# CLASS1.net
KiCad netlist of a schematic drawn in Altium Designer
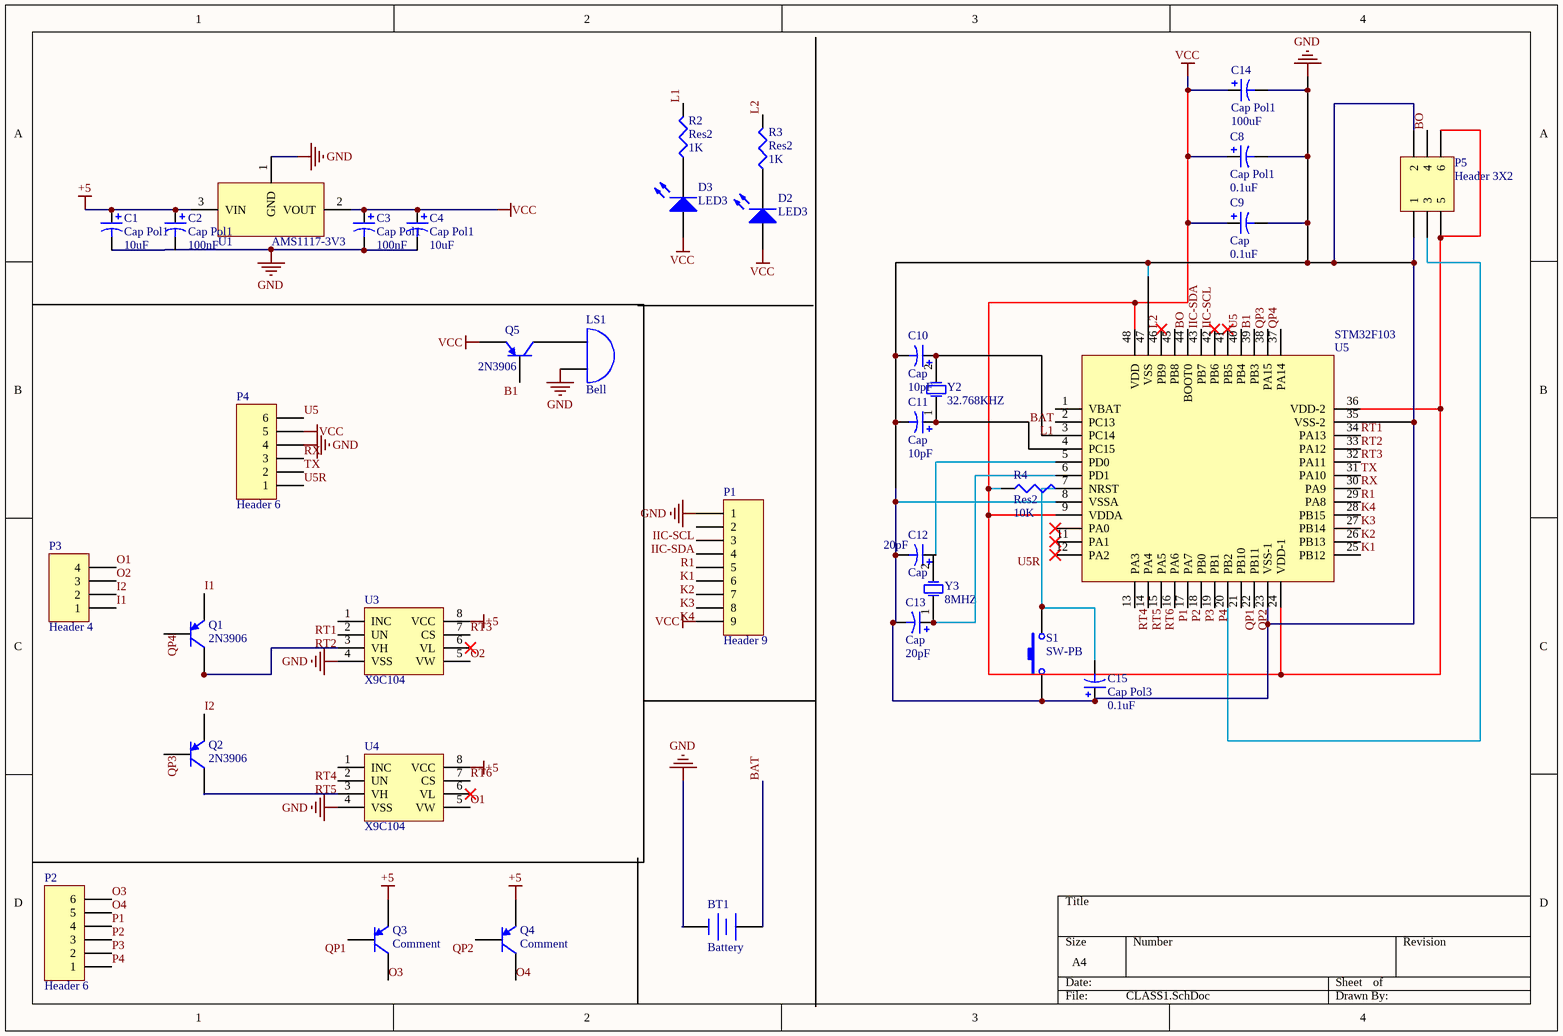
[diagram p0: CLASS1.SchDoc]

(export (version "E")
  (design (tool "Eeschema 10.0.6"))
  (components
    (comp (ref "BT1")
      (value "Battery")
      (footprint "BAT-2")
      (description "Multicell Battery")
      (fields (field (name "PUBLISHER") "Altium Limited"))
      (libsource (lib "Miscellaneous Devices") (part "Battery"))
    )
    (comp (ref "C1")
      (value "Cap Pol1")
      (footprint "C0805")
      (description "Polarized Capacitor (Surface Mount)")
      (fields (field (name "ALTIUM_VALUE") "10uF") (field (name "PUBLISHER") "Altium Limited"))
      (libsource (lib "Miscellaneous Devices") (part "Cap Pol3"))
    )
    (comp (ref "C2")
      (value "Cap Pol1")
      (footprint "C0805")
      (description "Polarized Capacitor (Surface Mount)")
      (fields (field (name "ALTIUM_VALUE") "100nF") (field (name "PUBLISHER") "Altium Limited"))
      (libsource (lib "Miscellaneous Devices") (part "Cap Pol3"))
    )
    (comp (ref "C3")
      (value "Cap Pol1")
      (footprint "C0805")
      (description "Polarized Capacitor (Surface Mount)")
      (fields (field (name "ALTIUM_VALUE") "100nF") (field (name "PUBLISHER") "Altium Limited"))
      (libsource (lib "Miscellaneous Devices") (part "Cap Pol3"))
    )
    (comp (ref "C4")
      (value "Cap Pol1")
      (footprint "C0805")
      (description "Polarized Capacitor (Surface Mount)")
      (fields (field (name "ALTIUM_VALUE") "10uF") (field (name "PUBLISHER") "Altium Limited"))
      (libsource (lib "Miscellaneous Devices") (part "Cap Pol3"))
    )
    (comp (ref "C8")
      (value "Cap Pol1")
      (footprint "C0805")
      (description "Polarized Capacitor (Surface Mount)")
      (fields (field (name "ALTIUM_VALUE") "0.1uF") (field (name "PUBLISHER") "Altium Limited"))
      (libsource (lib "Miscellaneous Devices") (part "Cap Pol3"))
    )
    (comp (ref "C9")
      (value "Cap")
      (footprint "C0805")
      (description "Polarized Capacitor (Surface Mount)")
      (fields (field (name "ALTIUM_VALUE") "0.1uF") (field (name "PUBLISHER") "Altium Limited"))
      (libsource (lib "Miscellaneous Devices") (part "Cap Pol3"))
    )
    (comp (ref "C10")
      (value "Cap")
      (footprint "C0805")
      (description "Polarized Capacitor (Surface Mount)")
      (fields (field (name "ALTIUM_VALUE") "10pF") (field (name "PUBLISHER") "Altium Limited"))
      (libsource (lib "Miscellaneous Devices") (part "Cap Pol3"))
    )
    (comp (ref "C11")
      (value "Cap")
      (footprint "C0805")
      (description "Polarized Capacitor (Surface Mount)")
      (fields (field (name "ALTIUM_VALUE") "10pF") (field (name "PUBLISHER") "Altium Limited"))
      (libsource (lib "Miscellaneous Devices") (part "Cap Pol3"))
    )
    (comp (ref "C12")
      (value "Cap")
      (footprint "C0805")
      (description "Polarized Capacitor (Surface Mount)")
      (fields (field (name "ALTIUM_VALUE") "20pF") (field (name "PUBLISHER") "Altium Limited"))
      (libsource (lib "Miscellaneous Devices") (part "Cap Pol3"))
    )
    (comp (ref "C13")
      (value "Cap")
      (footprint "C0805")
      (description "Polarized Capacitor (Surface Mount)")
      (fields (field (name "ALTIUM_VALUE") "20pF") (field (name "PUBLISHER") "Altium Limited"))
      (libsource (lib "Miscellaneous Devices") (part "Cap Pol3"))
    )
    (comp (ref "C14")
      (value "Cap Pol1")
      (footprint "A")
      (description "Polarized Capacitor (Radial)")
      (fields (field (name "ALTIUM_VALUE") "100uF") (field (name "PUBLISHER") "Altium Limited"))
      (libsource (lib "Miscellaneous Devices") (part "Cap Pol1"))
    )
    (comp (ref "C15")
      (value "Cap Pol3")
      (footprint "C0805")
      (description "Polarized Capacitor (Surface Mount)")
      (fields (field (name "ALTIUM_VALUE") "0.1uF") (field (name "PUBLISHER") "Altium Limited"))
      (libsource (lib "Miscellaneous Devices") (part "Cap Pol3"))
    )
    (comp (ref "D2")
      (value "LED3")
      (footprint "6-0805")
      (description "Typical BLUE SiC LED")
      (fields (field (name "PUBLISHER") "Altium Limited"))
      (libsource (lib "Miscellaneous Devices") (part "LED3"))
    )
    (comp (ref "D3")
      (value "LED3")
      (footprint "C0805")
      (description "Typical BLUE SiC LED")
      (fields (field (name "PUBLISHER") "Altium Limited"))
      (libsource (lib "Miscellaneous Devices") (part "LED3"))
    )
    (comp (ref "LS1")
      (value "Bell")
      (footprint "PIN2")
      (description "Electrical Bell")
      (fields (field (name "PUBLISHER") "Altium Limited"))
      (libsource (lib "Miscellaneous Devices") (part "Bell"))
    )
    (comp (ref "P1")
      (value "Header 9")
      (footprint "HDR1X9")
      (description "Header, 9-Pin")
      (fields (field (name "PUBLISHER") "Altium Limited"))
      (libsource (lib "Miscellaneous Connectors") (part "Header 9"))
    )
    (comp (ref "P2")
      (value "Header 6")
      (footprint "HDR1X6")
      (description "Header, 6-Pin")
      (fields (field (name "PUBLISHER") "Altium Limited"))
      (libsource (lib "Miscellaneous Connectors") (part "Header 6"))
    )
    (comp (ref "P3")
      (value "Header 4")
      (footprint "HDR1X4")
      (description "Header, 4-Pin")
      (fields (field (name "PUBLISHER") "Altium Limited"))
      (libsource (lib "Miscellaneous Connectors") (part "Header 4"))
    )
    (comp (ref "P4")
      (value "Header 6")
      (footprint "HDR1X6")
      (description "Header, 6-Pin")
      (fields (field (name "PUBLISHER") "Altium Limited"))
      (libsource (lib "Miscellaneous Connectors") (part "Header 6"))
    )
    (comp (ref "P5")
      (value "Header 3X2")
      (footprint "HDR2X3")
      (description "Header, 3-Pin, Dual row")
      (fields (field (name "PUBLISHER") "Altium Limited"))
      (libsource (lib "Miscellaneous Connectors") (part "Header 3X2"))
    )
    (comp (ref "Q1")
      (value "2N3906")
      (footprint "TO-92A")
      (description "PNP General Purpose Amplifier")
      (fields (field (name "PUBLISHER") "Altium Limited"))
      (libsource (lib "Miscellaneous Devices") (part "2N3906"))
    )
    (comp (ref "Q2")
      (value "2N3906")
      (footprint "TO-92A")
      (description "PNP General Purpose Amplifier")
      (fields (field (name "PUBLISHER") "Altium Limited"))
      (libsource (lib "Miscellaneous Devices") (part "2N3906"))
    )
    (comp (ref "Q3")
      (value "Comment")
      (footprint "TO-92A")
      (description "PNP General Purpose Amplifier")
      (fields (field (name "PUBLISHER") "Altium Limited"))
      (libsource (lib "Miscellaneous Devices") (part "2N3906"))
    )
    (comp (ref "Q4")
      (value "Comment")
      (footprint "TO-92A")
      (description "PNP General Purpose Amplifier")
      (fields (field (name "PUBLISHER") "Altium Limited"))
      (libsource (lib "Miscellaneous Devices") (part "2N3906"))
    )
    (comp (ref "Q5")
      (value "2N3906")
      (footprint "TO-92A")
      (description "PNP General Purpose Amplifier")
      (fields (field (name "PUBLISHER") "Altium Limited"))
      (libsource (lib "Miscellaneous Devices") (part "2N3906"))
    )
    (comp (ref "R2")
      (value "Res2")
      (footprint "J1-0603")
      (description "Resistor")
      (fields (field (name "ALTIUM_VALUE") "1K") (field (name "PUBLISHER") "Altium Limited"))
      (libsource (lib "Miscellaneous Devices") (part "Res3"))
    )
    (comp (ref "R3")
      (value "Res2")
      (footprint "J1-0603")
      (description "Resistor")
      (fields (field (name "ALTIUM_VALUE") "1K") (field (name "PUBLISHER") "Altium Limited"))
      (libsource (lib "Miscellaneous Devices") (part "Res3"))
    )
    (comp (ref "R4")
      (value "Res2")
      (footprint "J1-0603")
      (description "Resistor")
      (fields (field (name "ALTIUM_VALUE") "10K") (field (name "PUBLISHER") "Altium Limited"))
      (libsource (lib "Miscellaneous Devices") (part "Res3"))
    )
    (comp (ref "S1")
      (value "SW-PB")
      (footprint "SPST-2")
      (description "Switch")
      (fields (field (name "PUBLISHER") "Altium Limited"))
      (libsource (lib "Miscellaneous Devices") (part "SW-PB"))
    )
    (comp (ref "U1")
      (value "AMS1117-3V3")
      (footprint "AMS1117-3V3")
      (libsource (lib "Schlib STM") (part "AMS1117-3V3"))
    )
    (comp (ref "U3") (value "X9C104") (footprint "X9C104") (libsource (lib "Schlib STM") (part "xX9C104")))
    (comp (ref "U4") (value "X9C104") (footprint "X9C104") (libsource (lib "Schlib STM") (part "xX9C104")))
    (comp (ref "U5")
      (value "STM32F103")
      (footprint "STM32F103")
      (libsource (lib "Schlib STM") (part "STM32F103"))
    )
    (comp (ref "Y2")
      (value "32.768KHZ")
      (footprint "R38")
      (description "Crystal Oscillator")
      (fields (field (name "PUBLISHER") "Altium Limited"))
      (libsource (lib "Miscellaneous Devices") (part "XTAL"))
    )
    (comp (ref "Y3")
      (value "8MHZ")
      (footprint "R38")
      (description "Crystal Oscillator")
      (fields (field (name "PUBLISHER") "Altium Limited"))
      (libsource (lib "Miscellaneous Devices") (part "XTAL"))
    )
  )
  (nets
    (net (code "1") (name "+5") (class "Default")
      (node (ref "C1") (pin "1") (pinfunction "1_1") (pintype "passive"))
      (node (ref "C2") (pin "1") (pinfunction "1_1") (pintype "passive"))
      (node (ref "Q3") (pin "1") (pinfunction "E_1") (pintype "passive"))
      (node (ref "Q4") (pin "1") (pinfunction "E_1") (pintype "passive"))
      (node (ref "U1") (pin "3") (pinfunction "VIN_3") (pintype "power_in"))
      (node (ref "U3") (pin "8") (pinfunction "VCC_8") (pintype "power_in"))
      (node (ref "U4") (pin "8") (pinfunction "VCC_8") (pintype "power_in"))
    )
    (net (code "2") (name "/B1") (class "Default")
      (node (ref "Q5") (pin "2") (pinfunction "B_2") (pintype "passive"))
      (node (ref "U5") (pin "39") (pinfunction "PB3_39") (pintype "power_in"))
    )
    (net (code "3") (name "/BAT") (class "Default")
      (node (ref "BT1") (pin "1") (pinfunction "+_1") (pintype "passive"))
      (node (ref "U5") (pin "1") (pinfunction "VBAT_1") (pintype "power_in"))
    )
    (net (code "4") (name "/BO") (class "Default")
      (node (ref "P5") (pin "4") (pinfunction "4_4") (pintype "passive"))
      (node (ref "U5") (pin "44") (pinfunction "BOOT0_44") (pintype "power_in"))
    )
    (net (code "5") (name "/I1") (class "Default")
      (node (ref "P3") (pin "1") (pinfunction "1_1") (pintype "passive"))
      (node (ref "Q1") (pin "1") (pinfunction "E_1") (pintype "passive"))
    )
    (net (code "6") (name "/I2") (class "Default")
      (node (ref "P3") (pin "2") (pinfunction "2_2") (pintype "passive"))
      (node (ref "Q2") (pin "1") (pinfunction "E_1") (pintype "passive"))
    )
    (net (code "7") (name "/IIC-SCL") (class "Default")
      (node (ref "P1") (pin "2") (pinfunction "2_2") (pintype "passive"))
      (node (ref "U5") (pin "42") (pinfunction "PB6_42") (pintype "power_in"))
    )
    (net (code "8") (name "/IIC-SDA") (class "Default")
      (node (ref "P1") (pin "3") (pinfunction "3_3") (pintype "passive"))
      (node (ref "U5") (pin "43") (pinfunction "PB7_43") (pintype "power_in"))
    )
    (net (code "9") (name "/K1") (class "Default")
      (node (ref "P1") (pin "5") (pinfunction "5_5") (pintype "passive"))
      (node (ref "U5") (pin "25") (pinfunction "PB12_25") (pintype "power_in"))
    )
    (net (code "10") (name "/K2") (class "Default")
      (node (ref "P1") (pin "6") (pinfunction "6_6") (pintype "passive"))
      (node (ref "U5") (pin "26") (pinfunction "PB13_26") (pintype "power_in"))
    )
    (net (code "11") (name "/K3") (class "Default")
      (node (ref "P1") (pin "7") (pinfunction "7_7") (pintype "passive"))
      (node (ref "U5") (pin "27") (pinfunction "PB14_27") (pintype "power_in"))
    )
    (net (code "12") (name "/K4") (class "Default")
      (node (ref "P1") (pin "8") (pinfunction "8_8") (pintype "passive"))
      (node (ref "U5") (pin "28") (pinfunction "PB15_28") (pintype "power_in"))
    )
    (net (code "13") (name "/L1") (class "Default")
      (node (ref "R2") (pin "2") (pinfunction "2_2") (pintype "passive"))
      (node (ref "U5") (pin "2") (pinfunction "PC13_2") (pintype "power_in"))
    )
    (net (code "14") (name "/L2") (class "Default")
      (node (ref "R3") (pin "2") (pinfunction "2_2") (pintype "passive"))
      (node (ref "U5") (pin "46") (pinfunction "PB9_46") (pintype "power_in"))
    )
    (net (code "15") (name "/O1") (class "Default")
      (node (ref "P3") (pin "4") (pinfunction "4_4") (pintype "passive"))
      (node (ref "U4") (pin "5") (pinfunction "VW_5") (pintype "power_in"))
    )
    (net (code "16") (name "/O2") (class "Default")
      (node (ref "P3") (pin "3") (pinfunction "3_3") (pintype "passive"))
      (node (ref "U3") (pin "5") (pinfunction "VW_5") (pintype "power_in"))
    )
    (net (code "17") (name "/O3") (class "Default")
      (node (ref "P2") (pin "6") (pinfunction "6_6") (pintype "passive"))
      (node (ref "Q3") (pin "3") (pinfunction "C_3") (pintype "passive"))
    )
    (net (code "18") (name "/O4") (class "Default")
      (node (ref "P2") (pin "5") (pinfunction "5_5") (pintype "passive"))
      (node (ref "Q4") (pin "3") (pinfunction "C_3") (pintype "passive"))
    )
    (net (code "19") (name "/P1") (class "Default")
      (node (ref "P2") (pin "4") (pinfunction "4_4") (pintype "passive"))
      (node (ref "U5") (pin "16") (pinfunction "PA6_16") (pintype "power_in"))
    )
    (net (code "20") (name "/P2") (class "Default")
      (node (ref "P2") (pin "3") (pinfunction "3_3") (pintype "passive"))
      (node (ref "U5") (pin "17") (pinfunction "PA7_17") (pintype "power_in"))
    )
    (net (code "21") (name "/P3") (class "Default")
      (node (ref "P2") (pin "2") (pinfunction "2_2") (pintype "passive"))
      (node (ref "U5") (pin "18") (pinfunction "PB0_18") (pintype "power_in"))
    )
    (net (code "22") (name "/P4") (class "Default")
      (node (ref "P2") (pin "1") (pinfunction "1_1") (pintype "passive"))
      (node (ref "U5") (pin "19") (pinfunction "PB1_19") (pintype "power_in"))
    )
    (net (code "23") (name "/QP1") (class "Default")
      (node (ref "Q3") (pin "2") (pinfunction "B_2") (pintype "passive"))
      (node (ref "U5") (pin "21") (pinfunction "PB10_21") (pintype "power_in"))
    )
    (net (code "24") (name "/QP2") (class "Default")
      (node (ref "Q4") (pin "2") (pinfunction "B_2") (pintype "passive"))
      (node (ref "U5") (pin "22") (pinfunction "PB11_22") (pintype "power_in"))
    )
    (net (code "25") (name "/QP3") (class "Default")
      (node (ref "Q2") (pin "2") (pinfunction "B_2") (pintype "passive"))
      (node (ref "U5") (pin "38") (pinfunction "PA15_38") (pintype "power_in"))
    )
    (net (code "26") (name "/QP4") (class "Default")
      (node (ref "Q1") (pin "2") (pinfunction "B_2") (pintype "passive"))
      (node (ref "U5") (pin "37") (pinfunction "PA14_37") (pintype "power_in"))
    )
    (net (code "27") (name "/R1") (class "Default")
      (node (ref "P1") (pin "4") (pinfunction "4_4") (pintype "passive"))
      (node (ref "U5") (pin "29") (pinfunction "PA8_29") (pintype "power_in"))
    )
    (net (code "28") (name "/RT1") (class "Default")
      (node (ref "U3") (pin "1") (pinfunction "INC_1") (pintype "power_in"))
      (node (ref "U5") (pin "34") (pinfunction "PA13_34") (pintype "power_in"))
    )
    (net (code "29") (name "/RT2") (class "Default")
      (node (ref "U3") (pin "2") (pinfunction "UN_2") (pintype "power_in"))
      (node (ref "U5") (pin "33") (pinfunction "PA12_33") (pintype "power_in"))
    )
    (net (code "30") (name "/RT3") (class "Default")
      (node (ref "U3") (pin "7") (pinfunction "CS_7") (pintype "power_in"))
      (node (ref "U5") (pin "32") (pinfunction "PA11_32") (pintype "power_in"))
    )
    (net (code "31") (name "/RT4") (class "Default")
      (node (ref "U4") (pin "1") (pinfunction "INC_1") (pintype "power_in"))
      (node (ref "U5") (pin "13") (pinfunction "PA3_13") (pintype "power_in"))
    )
    (net (code "32") (name "/RT5") (class "Default")
      (node (ref "U4") (pin "2") (pinfunction "UN_2") (pintype "power_in"))
      (node (ref "U5") (pin "14") (pinfunction "PA4_14") (pintype "power_in"))
    )
    (net (code "33") (name "/RT6") (class "Default")
      (node (ref "U4") (pin "7") (pinfunction "CS_7") (pintype "power_in"))
      (node (ref "U5") (pin "15") (pinfunction "PA5_15") (pintype "power_in"))
    )
    (net (code "34") (name "/RX") (class "Default")
      (node (ref "P4") (pin "3") (pinfunction "3_3") (pintype "passive"))
      (node (ref "U5") (pin "30") (pinfunction "PA9_30") (pintype "power_in"))
    )
    (net (code "35") (name "/TX") (class "Default")
      (node (ref "P4") (pin "2") (pinfunction "2_2") (pintype "passive"))
      (node (ref "U5") (pin "31") (pinfunction "PA10_31") (pintype "power_in"))
    )
    (net (code "36") (name "/U5") (class "Default")
      (node (ref "P4") (pin "6") (pinfunction "6_6") (pintype "passive"))
      (node (ref "U5") (pin "40") (pinfunction "PB4_40") (pintype "power_in"))
    )
    (net (code "37") (name "/U5R") (class "Default")
      (node (ref "C15") (pin "2") (pinfunction "2_2") (pintype "passive"))
      (node (ref "P4") (pin "1") (pinfunction "1_1") (pintype "passive"))
      (node (ref "S1") (pin "1") (pinfunction "1_1") (pintype "passive"))
      (node (ref "U5") (pin "7") (pinfunction "NRST_7") (pintype "power_in"))
    )
    (net (code "38") (name "GND") (class "Default")
      (node (ref "BT1") (pin "2") (pinfunction "-_2") (pintype "passive"))
      (node (ref "C1") (pin "2") (pinfunction "2_2") (pintype "passive"))
      (node (ref "C10") (pin "2") (pinfunction "2_2") (pintype "passive"))
      (node (ref "C11") (pin "2") (pinfunction "2_2") (pintype "passive"))
      (node (ref "C12") (pin "2") (pinfunction "2_2") (pintype "passive"))
      (node (ref "C13") (pin "2") (pinfunction "2_2") (pintype "passive"))
      (node (ref "C14") (pin "2") (pinfunction "2_2") (pintype "passive"))
      (node (ref "C15") (pin "1") (pinfunction "1_1") (pintype "passive"))
      (node (ref "C3") (pin "2") (pinfunction "2_2") (pintype "passive"))
      (node (ref "C4") (pin "2") (pinfunction "2_2") (pintype "passive"))
      (node (ref "C8") (pin "2") (pinfunction "2_2") (pintype "passive"))
      (node (ref "C9") (pin "2") (pinfunction "2_2") (pintype "passive"))
      (node (ref "LS1") (pin "2") (pinfunction "B_2") (pintype "passive"))
      (node (ref "P1") (pin "1") (pinfunction "1_1") (pintype "passive"))
      (node (ref "P4") (pin "4") (pinfunction "4_4") (pintype "passive"))
      (node (ref "P5") (pin "1") (pinfunction "1_1") (pintype "passive"))
      (node (ref "P5") (pin "2") (pinfunction "2_2") (pintype "passive"))
      (node (ref "S1") (pin "2") (pinfunction "2_2") (pintype "passive"))
      (node (ref "U1") (pin "1") (pinfunction "GND_1") (pintype "power_in"))
      (node (ref "U3") (pin "4") (pinfunction "VSS_4") (pintype "power_in"))
      (node (ref "U4") (pin "4") (pinfunction "VSS_4") (pintype "power_in"))
      (node (ref "U5") (pin "23") (pinfunction "VSS-1_23") (pintype "power_in"))
      (node (ref "U5") (pin "35") (pinfunction "VSS-2_35") (pintype "power_in"))
      (node (ref "U5") (pin "47") (pinfunction "VSS_47") (pintype "power_in"))
      (node (ref "U5") (pin "8") (pinfunction "VSSA_8") (pintype "power_in"))
    )
    (net (code "39") (name "Net-(D2-K)") (class "Default")
      (node (ref "D2") (pin "2") (pinfunction "K_2") (pintype "passive"))
      (node (ref "R3") (pin "1") (pinfunction "1_1") (pintype "passive"))
    )
    (net (code "40") (name "Net-(D3-K)") (class "Default")
      (node (ref "D3") (pin "2") (pinfunction "K_2") (pintype "passive"))
      (node (ref "R2") (pin "1") (pinfunction "1_1") (pintype "passive"))
    )
    (net (code "41") (name "Net-(LS1-A)") (class "Default")
      (node (ref "LS1") (pin "1") (pinfunction "A_1") (pintype "passive"))
      (node (ref "Q5") (pin "3") (pinfunction "C_3") (pintype "passive"))
    )
    (net (code "42") (name "Net-(Q1-C)") (class "Default")
      (node (ref "Q1") (pin "3") (pinfunction "C_3") (pintype "passive"))
      (node (ref "U3") (pin "3") (pinfunction "VH_3") (pintype "power_in"))
    )
    (net (code "43") (name "Net-(Q2-C)") (class "Default")
      (node (ref "Q2") (pin "3") (pinfunction "C_3") (pintype "passive"))
      (node (ref "U4") (pin "3") (pinfunction "VH_3") (pintype "power_in"))
    )
    (net (code "44") (name "Net-(U5-PB2)") (class "Default")
      (node (ref "P5") (pin "3") (pinfunction "3_3") (pintype "passive"))
      (node (ref "U5") (pin "20") (pinfunction "PB2_20") (pintype "power_in"))
    )
    (net (code "45") (name "Net-(U5-PC14)") (class "Default")
      (node (ref "C10") (pin "1") (pinfunction "1_1") (pintype "passive"))
      (node (ref "U5") (pin "3") (pinfunction "PC14_3") (pintype "power_in"))
      (node (ref "Y2") (pin "2") (pinfunction "OSC2_2") (pintype "passive"))
    )
    (net (code "46") (name "Net-(U5-PC15)") (class "Default")
      (node (ref "C11") (pin "1") (pinfunction "1_1") (pintype "passive"))
      (node (ref "U5") (pin "4") (pinfunction "PC15_4") (pintype "power_in"))
      (node (ref "Y2") (pin "1") (pinfunction "OSC1_1") (pintype "passive"))
    )
    (net (code "47") (name "Net-(U5-PD0)") (class "Default")
      (node (ref "C12") (pin "1") (pinfunction "1_1") (pintype "passive"))
      (node (ref "U5") (pin "5") (pinfunction "PD0_5") (pintype "power_in"))
    )
    (net (code "48") (name "Net-(U5-PD1)") (class "Default")
      (node (ref "C13") (pin "1") (pinfunction "1_1") (pintype "passive"))
      (node (ref "U5") (pin "6") (pinfunction "PD1_6") (pintype "power_in"))
      (node (ref "Y3") (pin "1") (pinfunction "OSC1_1") (pintype "passive"))
    )
    (net (code "49") (name "VCC") (class "Default")
      (node (ref "C14") (pin "1") (pinfunction "1_1") (pintype "passive"))
      (node (ref "C3") (pin "1") (pinfunction "1_1") (pintype "passive"))
      (node (ref "C4") (pin "1") (pinfunction "1_1") (pintype "passive"))
      (node (ref "C8") (pin "1") (pinfunction "1_1") (pintype "passive"))
      (node (ref "C9") (pin "1") (pinfunction "1_1") (pintype "passive"))
      (node (ref "D2") (pin "1") (pinfunction "A_1") (pintype "passive"))
      (node (ref "D3") (pin "1") (pinfunction "A_1") (pintype "passive"))
      (node (ref "P1") (pin "9") (pinfunction "9_9") (pintype "passive"))
      (node (ref "P4") (pin "5") (pinfunction "5_5") (pintype "passive"))
      (node (ref "P5") (pin "5") (pinfunction "5_5") (pintype "passive"))
      (node (ref "P5") (pin "6") (pinfunction "6_6") (pintype "passive"))
      (node (ref "Q5") (pin "1") (pinfunction "E_1") (pintype "passive"))
      (node (ref "R4") (pin "1") (pinfunction "1_1") (pintype "passive"))
      (node (ref "U1") (pin "2") (pinfunction "VOUT_2") (pintype "power_in"))
      (node (ref "U5") (pin "24") (pinfunction "VDD-1_24") (pintype "power_in"))
      (node (ref "U5") (pin "36") (pinfunction "VDD-2_36") (pintype "power_in"))
      (node (ref "U5") (pin "48") (pinfunction "VDD_48") (pintype "power_in"))
      (node (ref "U5") (pin "9") (pinfunction "VDDA_9") (pintype "power_in"))
    )
    (net (code "50") (name "unconnected-(C2-Pad2)") (class "Default")
      (node (ref "C2") (pin "2") (pinfunction "2_2") (pintype "passive"))
    )
    (net (code "51") (name "unconnected-(R4-Pad2)") (class "Default")
      (node (ref "R4") (pin "2") (pinfunction "2_2") (pintype "passive"))
    )
    (net (code "52") (name "unconnected-(U3-VL-Pad6)") (class "Default")
      (node (ref "U3") (pin "6") (pinfunction "VL_6") (pintype "power_in+no_connect"))
    )
    (net (code "53") (name "unconnected-(U4-VL-Pad6)") (class "Default")
      (node (ref "U4") (pin "6") (pinfunction "VL_6") (pintype "power_in+no_connect"))
    )
    (net (code "54") (name "unconnected-(U5-PA0-Pad10)") (class "Default")
      (node (ref "U5") (pin "10") (pinfunction "PA0_10") (pintype "power_in+no_connect"))
    )
    (net (code "55") (name "unconnected-(U5-PA1-Pad11)") (class "Default")
      (node (ref "U5") (pin "11") (pinfunction "PA1_11") (pintype "power_in+no_connect"))
    )
    (net (code "56") (name "unconnected-(U5-PA2-Pad12)") (class "Default")
      (node (ref "U5") (pin "12") (pinfunction "PA2_12") (pintype "power_in+no_connect"))
    )
    (net (code "57") (name "unconnected-(U5-PB5-Pad41)") (class "Default")
      (node (ref "U5") (pin "41") (pinfunction "PB5_41") (pintype "power_in+no_connect"))
    )
    (net (code "58") (name "unconnected-(U5-PB8-Pad45)") (class "Default")
      (node (ref "U5") (pin "45") (pinfunction "PB8_45") (pintype "power_in"))
    )
    (net (code "59") (name "unconnected-(Y3-OSC2-Pad2)") (class "Default")
      (node (ref "Y3") (pin "2") (pinfunction "OSC2_2") (pintype "passive"))
    )
  )
)
